# LCDserie.net
KiCad netlist of a schematic drawn in EAGLE
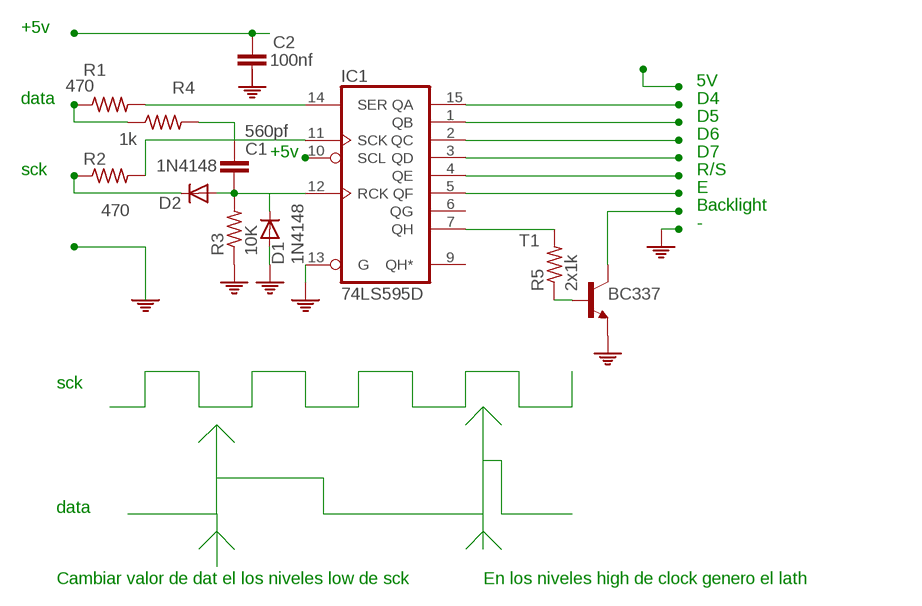
[diagram p0: schematic, sheet 1]

(export (version "E")
  (design (tool "Eeschema 10.0.6"))
  (components
    (comp (ref "C1")
      (value "560pf")
      (footprint "eagle-import:C025_050-035X075")
      (libsource (lib "eagle-import") (part "C-EU025_050-035X075"))
    )
    (comp (ref "C2")
      (value "100nf")
      (footprint "eagle-import:C025_050-035X075")
      (libsource (lib "eagle-import") (part "C-EU025_050-035X075"))
    )
    (comp (ref "D1")
      (value "1N4148")
      (footprint "eagle-import:DO35-7")
      (libsource (lib "eagle-import") (part "1N4148DO35-7"))
    )
    (comp (ref "D2")
      (value "1N4148")
      (footprint "eagle-import:DO35-7")
      (libsource (lib "eagle-import") (part "1N4148DO35-7"))
    )
    (comp (ref "IC1")
      (value "74LS595D")
      (footprint "eagle-import:SO16")
      (libsource (lib "eagle-import") (part "74595DLS"))
    )
    (comp (ref "R1")
      (value "470")
      (footprint "eagle-import:0207_7")
      (libsource (lib "eagle-import") (part "R-US_0207/7"))
    )
    (comp (ref "R2")
      (value "470")
      (footprint "eagle-import:0207_7")
      (libsource (lib "eagle-import") (part "R-US_0207/7"))
    )
    (comp (ref "R3")
      (value "10K")
      (footprint "eagle-import:0207_7")
      (libsource (lib "eagle-import") (part "R-US_0207/7"))
    )
    (comp (ref "R4")
      (value "1k")
      (footprint "eagle-import:0207_7")
      (libsource (lib "eagle-import") (part "R-US_0207/7"))
    )
    (comp (ref "R5")
      (value "2x1k")
      (footprint "eagle-import:0207_7")
      (libsource (lib "eagle-import") (part "R-US_0207/7"))
    )
    (comp (ref "T1")
      (value "BC337")
      (footprint "eagle-import:TO92")
      (libsource (lib "eagle-import") (part "BC337"))
    )
  )
  (nets
    (net (code "1") (name "Net-(C1-Pad1)") (class "Default")
      (node (ref "C1") (pin "1") (pinfunction "1_1") (pintype "passive"))
      (node (ref "R4") (pin "2") (pinfunction "2_2") (pintype "passive"))
    )
    (net (code "2") (name "Net-(D2-PadC)") (class "Default")
      (node (ref "D2") (pin "C") (pinfunction "C_C") (pintype "passive"))
      (node (ref "R2") (pin "1") (pinfunction "1_1") (pintype "passive"))
    )
    (net (code "3") (name "Net-(IC1A-QH)") (class "Default")
      (node (ref "IC1") (pin "7") (pinfunction "QH_7") (pintype "tri_state"))
      (node (ref "R5") (pin "2") (pinfunction "2_2") (pintype "passive"))
    )
    (net (code "4") (name "Net-(IC1A-RCK)") (class "Default")
      (node (ref "C1") (pin "2") (pinfunction "2_2") (pintype "passive"))
      (node (ref "D1") (pin "C") (pinfunction "C_C") (pintype "passive"))
      (node (ref "D2") (pin "A") (pinfunction "A_A") (pintype "passive"))
      (node (ref "IC1") (pin "12") (pinfunction "RCK_12") (pintype "input"))
      (node (ref "R3") (pin "2") (pinfunction "2_2") (pintype "passive"))
    )
    (net (code "5") (name "Net-(IC1A-SCK)") (class "Default")
      (node (ref "IC1") (pin "11") (pinfunction "SCK_11") (pintype "input"))
      (node (ref "R2") (pin "2") (pinfunction "2_2") (pintype "passive"))
    )
    (net (code "6") (name "Net-(IC1A-SER)") (class "Default")
      (node (ref "IC1") (pin "14") (pinfunction "SER_14") (pintype "input"))
      (node (ref "R1") (pin "2") (pinfunction "2_2") (pintype "passive"))
    )
    (net (code "7") (name "Net-(R1-Pad1)") (class "Default")
      (node (ref "R1") (pin "1") (pinfunction "1_1") (pintype "passive"))
      (node (ref "R4") (pin "1") (pinfunction "1_1") (pintype "passive"))
    )
    (net (code "8") (name "Net-(T1-B)") (class "Default")
      (node (ref "R5") (pin "1") (pinfunction "1_1") (pintype "passive"))
      (node (ref "T1") (pin "2") (pinfunction "B_2") (pintype "passive"))
    )
    (net (code "9") (name "PE") (class "Default")
      (node (ref "D1") (pin "A") (pinfunction "A_A") (pintype "passive"))
      (node (ref "IC1") (pin "13") (pinfunction "G_13") (pintype "input"))
      (node (ref "R3") (pin "1") (pinfunction "1_1") (pintype "passive"))
      (node (ref "T1") (pin "1") (pinfunction "E_1") (pintype "passive"))
    )
    (net (code "10") (name "unconnected-(C2-Pad1)") (class "Default")
      (node (ref "C2") (pin "1") (pinfunction "1_1") (pintype "passive"))
    )
    (net (code "11") (name "unconnected-(C2-Pad2)") (class "Default")
      (node (ref "C2") (pin "2") (pinfunction "2_2") (pintype "passive"))
    )
    (net (code "12") (name "unconnected-(IC1A-QA-Pad15)") (class "Default")
      (node (ref "IC1") (pin "15") (pinfunction "QA_15") (pintype "tri_state"))
    )
    (net (code "13") (name "unconnected-(IC1A-QB-Pad1)") (class "Default")
      (node (ref "IC1") (pin "1") (pinfunction "QB_1") (pintype "tri_state"))
    )
    (net (code "14") (name "unconnected-(IC1A-QC-Pad2)") (class "Default")
      (node (ref "IC1") (pin "2") (pinfunction "QC_2") (pintype "tri_state"))
    )
    (net (code "15") (name "unconnected-(IC1A-QD-Pad3)") (class "Default")
      (node (ref "IC1") (pin "3") (pinfunction "QD_3") (pintype "tri_state"))
    )
    (net (code "16") (name "unconnected-(IC1A-QE-Pad4)") (class "Default")
      (node (ref "IC1") (pin "4") (pinfunction "QE_4") (pintype "tri_state"))
    )
    (net (code "17") (name "unconnected-(IC1A-QF-Pad5)") (class "Default")
      (node (ref "IC1") (pin "5") (pinfunction "QF_5") (pintype "tri_state"))
    )
    (net (code "18") (name "unconnected-(IC1A-QG-Pad6)") (class "Default")
      (node (ref "IC1") (pin "6") (pinfunction "QG_6") (pintype "tri_state"))
    )
    (net (code "19") (name "unconnected-(IC1A-QH*-Pad9)") (class "Default")
      (node (ref "IC1") (pin "9") (pinfunction "QH*_9") (pintype "tri_state"))
    )
    (net (code "20") (name "unconnected-(IC1A-SCL-Pad10)") (class "Default")
      (node (ref "IC1") (pin "10") (pinfunction "SCL_10") (pintype "input"))
    )
    (net (code "21") (name "unconnected-(T1-C-Pad3)") (class "Default")
      (node (ref "T1") (pin "3") (pinfunction "C_3") (pintype "passive"))
    )
  )
)
